# Driver.net
KiCad netlist of a schematic drawn in EAGLE
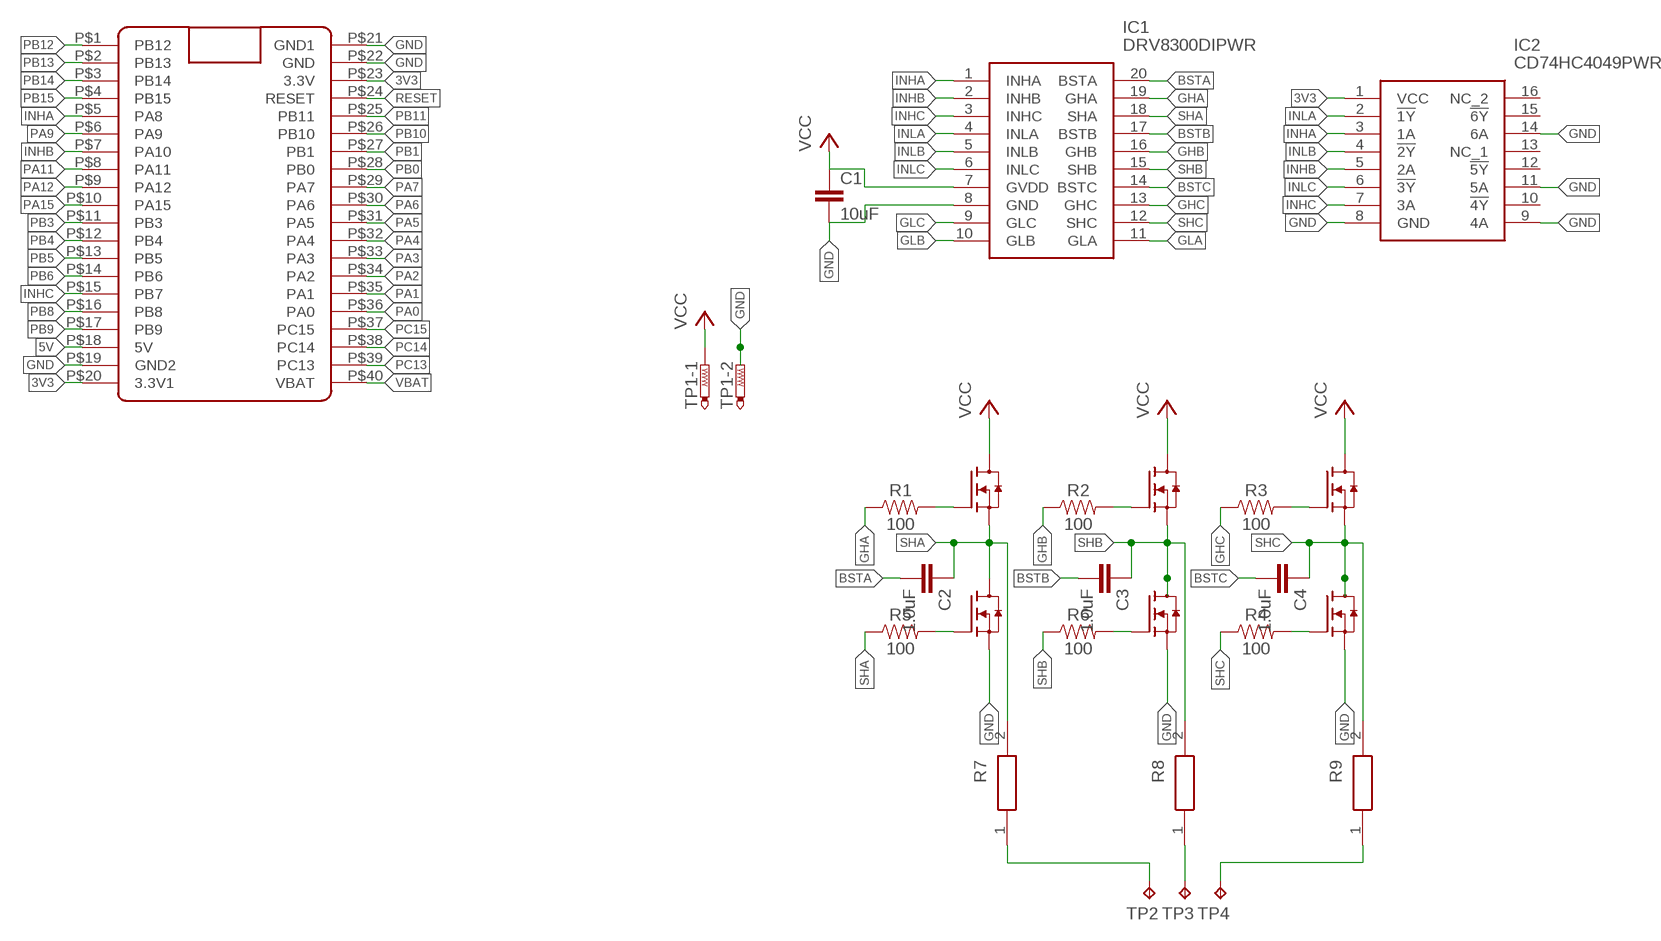
[diagram p0: schematic, sheet 1]

(export (version "E")
  (design (tool "Eeschema 10.0.6"))
  (components
    (comp (ref "C1")
      (value "10uF")
      (footprint "eagle-import:0603")
      (libsource (lib "eagle-import") (part "10UF-0603-6.3V-20%"))
    )
    (comp (ref "C2")
      (value "1.0uF")
      (footprint "eagle-import:0603")
      (libsource (lib "eagle-import") (part "1.0UF-0603-16V-10%"))
    )
    (comp (ref "C3")
      (value "1.0uF")
      (footprint "eagle-import:0603")
      (libsource (lib "eagle-import") (part "1.0UF-0603-16V-10%"))
    )
    (comp (ref "C4")
      (value "1.0uF")
      (footprint "eagle-import:0603")
      (libsource (lib "eagle-import") (part "1.0UF-0603-16V-10%"))
    )
    (comp (ref "IC1")
      (value "DRV8300DIPWR")
      (footprint "eagle-import:SOP65P640X120-20N")
      (fields (field (name "MOUSER_PART_NUMBER") "595-DRV8300DIPWR"))
      (libsource (lib "eagle-import") (part "DRV8300DIPWR"))
    )
    (comp (ref "IC2")
      (value "CD74HC4049PWR")
      (footprint "eagle-import:SOP65P640X120-16N")
      (fields (field (name "MOUSER_PART_NUMBER") "595-CD74HC4049PWR"))
      (libsource (lib "eagle-import") (part "CD74HC4049PWR"))
    )
    (comp (ref "R1")
      (value "100")
      (footprint "eagle-import:0603")
      (libsource (lib "eagle-import") (part "100OHM-0603-1/10W-1%"))
    )
    (comp (ref "R2")
      (value "100")
      (footprint "eagle-import:0603")
      (libsource (lib "eagle-import") (part "100OHM-0603-1/10W-1%"))
    )
    (comp (ref "R3")
      (value "100")
      (footprint "eagle-import:0603")
      (libsource (lib "eagle-import") (part "100OHM-0603-1/10W-1%"))
    )
    (comp (ref "R4")
      (value "100")
      (footprint "eagle-import:0603")
      (libsource (lib "eagle-import") (part "100OHM-0603-1/10W-1%"))
    )
    (comp (ref "R5")
      (value "100")
      (footprint "eagle-import:0603")
      (libsource (lib "eagle-import") (part "100OHM-0603-1/10W-1%"))
    )
    (comp (ref "R6")
      (value "100")
      (footprint "eagle-import:0603")
      (libsource (lib "eagle-import") (part "100OHM-0603-1/10W-1%"))
    )
    (comp (ref "R7")
      (value "CR2512-FX-51R1ELF")
      (footprint "eagle-import:RESC6331X75N")
      (fields (field (name "MOUSER_PART_NUMBER") "652-CR2512FX51R1ELF"))
      (libsource (lib "eagle-import") (part "CR2512-FX-51R1ELF"))
    )
    (comp (ref "R8")
      (value "CR2512-FX-51R1ELF")
      (footprint "eagle-import:RESC6331X75N")
      (fields (field (name "MOUSER_PART_NUMBER") "652-CR2512FX51R1ELF"))
      (libsource (lib "eagle-import") (part "CR2512-FX-51R1ELF"))
    )
    (comp (ref "R9")
      (value "CR2512-FX-51R1ELF")
      (footprint "eagle-import:RESC6331X75N")
      (fields (field (name "MOUSER_PART_NUMBER") "652-CR2512FX51R1ELF"))
      (libsource (lib "eagle-import") (part "CR2512-FX-51R1ELF"))
    )
    (comp (ref "TP1")
      (value "PTR2")
      (footprint "eagle-import:P2-38-17")
      (libsource (lib "eagle-import") (part "PTR2"))
    )
    (comp (ref "TP2")
      (value "TPTP20SQ")
      (footprint "eagle-import:TP20SQ")
      (libsource (lib "eagle-import") (part "TPTP20SQ"))
    )
    (comp (ref "TP3")
      (value "TPTP20SQ")
      (footprint "eagle-import:TP20SQ")
      (libsource (lib "eagle-import") (part "TPTP20SQ"))
    )
    (comp (ref "TP4")
      (value "TPTP20SQ")
      (footprint "eagle-import:TP20SQ")
      (libsource (lib "eagle-import") (part "TPTP20SQ"))
    )
    (comp (ref "U$1")
      (value "BLUE_PILL")
      (footprint "eagle-import:BLUE_PILL")
      (libsource (lib "eagle-import") (part "BLUE_PILL"))
    )
    (comp (ref "U$2")
      (value "IRLR7843")
      (footprint "eagle-import:TO252")
      (libsource (lib "eagle-import") (part "IRLR7843"))
    )
    (comp (ref "U$3")
      (value "IRLR7843")
      (footprint "eagle-import:TO252")
      (libsource (lib "eagle-import") (part "IRLR7843"))
    )
    (comp (ref "U$4")
      (value "IRLR7843")
      (footprint "eagle-import:TO252")
      (libsource (lib "eagle-import") (part "IRLR7843"))
    )
    (comp (ref "U$5")
      (value "IRLR7843")
      (footprint "eagle-import:TO252")
      (libsource (lib "eagle-import") (part "IRLR7843"))
    )
    (comp (ref "U$6")
      (value "IRLR7843")
      (footprint "eagle-import:TO252")
      (libsource (lib "eagle-import") (part "IRLR7843"))
    )
    (comp (ref "U$7")
      (value "IRLR7843")
      (footprint "eagle-import:TO252")
      (libsource (lib "eagle-import") (part "IRLR7843"))
    )
  )
  (nets
    (net (code "1") (name "3V3") (class "Default")
      (node (ref "IC2") (pin "1") (pinfunction "VCC_1") (pintype "bidirectional"))
      (node (ref "U$1") (pin "P$20") (pinfunction "3.3V1_P$20") (pintype "bidirectional"))
      (node (ref "U$1") (pin "P$23") (pinfunction "3.3V_P$23") (pintype "bidirectional"))
    )
    (net (code "2") (name "5V") (class "Default")
      (node (ref "U$1") (pin "P$18") (pinfunction "5V_P$18") (pintype "bidirectional"))
    )
    (net (code "3") (name "BSTA") (class "Default")
      (node (ref "C2") (pin "2") (pinfunction "2_2") (pintype "passive"))
      (node (ref "IC1") (pin "20") (pinfunction "BSTA_20") (pintype "bidirectional"))
    )
    (net (code "4") (name "BSTB") (class "Default")
      (node (ref "C3") (pin "2") (pinfunction "2_2") (pintype "passive"))
      (node (ref "IC1") (pin "17") (pinfunction "BSTB_17") (pintype "bidirectional"))
    )
    (net (code "5") (name "BSTC") (class "Default")
      (node (ref "C4") (pin "2") (pinfunction "2_2") (pintype "passive"))
      (node (ref "IC1") (pin "14") (pinfunction "BSTC_14") (pintype "bidirectional"))
    )
    (net (code "6") (name "GHA") (class "Default")
      (node (ref "IC1") (pin "19") (pinfunction "GHA_19") (pintype "bidirectional"))
      (node (ref "R1") (pin "1") (pinfunction "1_1") (pintype "passive"))
    )
    (net (code "7") (name "GHB") (class "Default")
      (node (ref "IC1") (pin "16") (pinfunction "GHB_16") (pintype "bidirectional"))
      (node (ref "R2") (pin "1") (pinfunction "1_1") (pintype "passive"))
    )
    (net (code "8") (name "GHC") (class "Default")
      (node (ref "IC1") (pin "13") (pinfunction "GHC_13") (pintype "bidirectional"))
      (node (ref "R3") (pin "1") (pinfunction "1_1") (pintype "passive"))
    )
    (net (code "9") (name "GLA") (class "Default")
      (node (ref "IC1") (pin "11") (pinfunction "GLA_11") (pintype "bidirectional"))
    )
    (net (code "10") (name "GLB") (class "Default")
      (node (ref "IC1") (pin "10") (pinfunction "GLB_10") (pintype "bidirectional"))
    )
    (net (code "11") (name "GLC") (class "Default")
      (node (ref "IC1") (pin "9") (pinfunction "GLC_9") (pintype "bidirectional"))
    )
    (net (code "12") (name "GND") (class "Default")
      (node (ref "C1") (pin "2") (pinfunction "2_2") (pintype "passive"))
      (node (ref "IC1") (pin "8") (pinfunction "GND_8") (pintype "bidirectional"))
      (node (ref "IC2") (pin "11") (pinfunction "5A_11") (pintype "bidirectional"))
      (node (ref "IC2") (pin "14") (pinfunction "6A_14") (pintype "bidirectional"))
      (node (ref "IC2") (pin "8") (pinfunction "GND_8") (pintype "bidirectional"))
      (node (ref "IC2") (pin "9") (pinfunction "4A_9") (pintype "bidirectional"))
      (node (ref "TP1") (pin "TP-2") (pinfunction "TP_TP-2") (pintype "input"))
      (node (ref "U$1") (pin "P$19") (pinfunction "GND2_P$19") (pintype "bidirectional"))
      (node (ref "U$1") (pin "P$21") (pinfunction "GND1_P$21") (pintype "power_in"))
      (node (ref "U$1") (pin "P$22") (pinfunction "GND_P$22") (pintype "bidirectional"))
      (node (ref "U$3") (pin "2") (pinfunction "S_2") (pintype "passive"))
      (node (ref "U$5") (pin "2") (pinfunction "S_2") (pintype "passive"))
      (node (ref "U$7") (pin "2") (pinfunction "S_2") (pintype "passive"))
    )
    (net (code "13") (name "INHA") (class "Default")
      (node (ref "IC1") (pin "1") (pinfunction "INHA_1") (pintype "bidirectional"))
      (node (ref "IC2") (pin "3") (pinfunction "1A_3") (pintype "bidirectional"))
      (node (ref "U$1") (pin "P$5") (pinfunction "PA8_P$5") (pintype "bidirectional"))
    )
    (net (code "14") (name "INHB") (class "Default")
      (node (ref "IC1") (pin "2") (pinfunction "INHB_2") (pintype "bidirectional"))
      (node (ref "IC2") (pin "5") (pinfunction "2A_5") (pintype "bidirectional"))
      (node (ref "U$1") (pin "P$7") (pinfunction "PA10_P$7") (pintype "bidirectional"))
    )
    (net (code "15") (name "INHC") (class "Default")
      (node (ref "IC1") (pin "3") (pinfunction "INHC_3") (pintype "bidirectional"))
      (node (ref "IC2") (pin "7") (pinfunction "3A_7") (pintype "bidirectional"))
      (node (ref "U$1") (pin "P$15") (pinfunction "PB7_P$15") (pintype "bidirectional"))
    )
    (net (code "16") (name "INLA") (class "Default")
      (node (ref "IC1") (pin "4") (pinfunction "INLA_4") (pintype "bidirectional"))
      (node (ref "IC2") (pin "2") (pinfunction "~{1Y}_2") (pintype "bidirectional"))
    )
    (net (code "17") (name "INLB") (class "Default")
      (node (ref "IC1") (pin "5") (pinfunction "INLB_5") (pintype "bidirectional"))
      (node (ref "IC2") (pin "4") (pinfunction "~{2Y}_4") (pintype "bidirectional"))
    )
    (net (code "18") (name "INLC") (class "Default")
      (node (ref "IC1") (pin "6") (pinfunction "INLC_6") (pintype "bidirectional"))
      (node (ref "IC2") (pin "6") (pinfunction "~{3Y}_6") (pintype "bidirectional"))
    )
    (net (code "19") (name "Net-(R7-Pad1)") (class "Default")
      (node (ref "R7") (pin "1") (pinfunction "1_1") (pintype "bidirectional"))
      (node (ref "TP2") (pin "TP") (pinfunction "TP_TP") (pintype "input"))
    )
    (net (code "20") (name "Net-(R8-Pad1)") (class "Default")
      (node (ref "R8") (pin "1") (pinfunction "1_1") (pintype "bidirectional"))
      (node (ref "TP3") (pin "TP") (pinfunction "TP_TP") (pintype "input"))
    )
    (net (code "21") (name "Net-(R9-Pad1)") (class "Default")
      (node (ref "R9") (pin "1") (pinfunction "1_1") (pintype "bidirectional"))
      (node (ref "TP4") (pin "TP") (pinfunction "TP_TP") (pintype "input"))
    )
    (net (code "22") (name "Net-(U$2-G)") (class "Default")
      (node (ref "R1") (pin "2") (pinfunction "2_2") (pintype "passive"))
      (node (ref "U$2") (pin "1") (pinfunction "G_1") (pintype "passive"))
    )
    (net (code "23") (name "Net-(U$3-G)") (class "Default")
      (node (ref "R5") (pin "2") (pinfunction "2_2") (pintype "passive"))
      (node (ref "U$3") (pin "1") (pinfunction "G_1") (pintype "passive"))
    )
    (net (code "24") (name "Net-(U$4-G)") (class "Default")
      (node (ref "R2") (pin "2") (pinfunction "2_2") (pintype "passive"))
      (node (ref "U$4") (pin "1") (pinfunction "G_1") (pintype "passive"))
    )
    (net (code "25") (name "Net-(U$5-G)") (class "Default")
      (node (ref "R6") (pin "2") (pinfunction "2_2") (pintype "passive"))
      (node (ref "U$5") (pin "1") (pinfunction "G_1") (pintype "passive"))
    )
    (net (code "26") (name "Net-(U$6-G)") (class "Default")
      (node (ref "R3") (pin "2") (pinfunction "2_2") (pintype "passive"))
      (node (ref "U$6") (pin "1") (pinfunction "G_1") (pintype "passive"))
    )
    (net (code "27") (name "Net-(U$7-G)") (class "Default")
      (node (ref "R4") (pin "2") (pinfunction "2_2") (pintype "passive"))
      (node (ref "U$7") (pin "1") (pinfunction "G_1") (pintype "passive"))
    )
    (net (code "28") (name "PA0") (class "Default")
      (node (ref "U$1") (pin "P$36") (pinfunction "PA0_P$36") (pintype "bidirectional"))
    )
    (net (code "29") (name "PA1") (class "Default")
      (node (ref "U$1") (pin "P$35") (pinfunction "PA1_P$35") (pintype "bidirectional"))
    )
    (net (code "30") (name "PA2") (class "Default")
      (node (ref "U$1") (pin "P$34") (pinfunction "PA2_P$34") (pintype "bidirectional"))
    )
    (net (code "31") (name "PA3") (class "Default")
      (node (ref "U$1") (pin "P$33") (pinfunction "PA3_P$33") (pintype "bidirectional"))
    )
    (net (code "32") (name "PA4") (class "Default")
      (node (ref "U$1") (pin "P$32") (pinfunction "PA4_P$32") (pintype "bidirectional"))
    )
    (net (code "33") (name "PA5") (class "Default")
      (node (ref "U$1") (pin "P$31") (pinfunction "PA5_P$31") (pintype "bidirectional"))
    )
    (net (code "34") (name "PA6") (class "Default")
      (node (ref "U$1") (pin "P$30") (pinfunction "PA6_P$30") (pintype "bidirectional"))
    )
    (net (code "35") (name "PA7") (class "Default")
      (node (ref "U$1") (pin "P$29") (pinfunction "PA7_P$29") (pintype "bidirectional"))
    )
    (net (code "36") (name "PA9") (class "Default")
      (node (ref "U$1") (pin "P$6") (pinfunction "PA9_P$6") (pintype "bidirectional"))
    )
    (net (code "37") (name "PA11") (class "Default")
      (node (ref "U$1") (pin "P$8") (pinfunction "PA11_P$8") (pintype "bidirectional"))
    )
    (net (code "38") (name "PA12") (class "Default")
      (node (ref "U$1") (pin "P$9") (pinfunction "PA12_P$9") (pintype "bidirectional"))
    )
    (net (code "39") (name "PA15") (class "Default")
      (node (ref "U$1") (pin "P$10") (pinfunction "PA15_P$10") (pintype "bidirectional"))
    )
    (net (code "40") (name "PB0") (class "Default")
      (node (ref "U$1") (pin "P$28") (pinfunction "PB0_P$28") (pintype "bidirectional"))
    )
    (net (code "41") (name "PB1") (class "Default")
      (node (ref "U$1") (pin "P$27") (pinfunction "PB1_P$27") (pintype "bidirectional"))
    )
    (net (code "42") (name "PB3") (class "Default")
      (node (ref "U$1") (pin "P$11") (pinfunction "PB3_P$11") (pintype "bidirectional"))
    )
    (net (code "43") (name "PB4") (class "Default")
      (node (ref "U$1") (pin "P$12") (pinfunction "PB4_P$12") (pintype "bidirectional"))
    )
    (net (code "44") (name "PB5") (class "Default")
      (node (ref "U$1") (pin "P$13") (pinfunction "PB5_P$13") (pintype "bidirectional"))
    )
    (net (code "45") (name "PB6") (class "Default")
      (node (ref "U$1") (pin "P$14") (pinfunction "PB6_P$14") (pintype "bidirectional"))
    )
    (net (code "46") (name "PB8") (class "Default")
      (node (ref "U$1") (pin "P$16") (pinfunction "PB8_P$16") (pintype "bidirectional"))
    )
    (net (code "47") (name "PB9") (class "Default")
      (node (ref "U$1") (pin "P$17") (pinfunction "PB9_P$17") (pintype "bidirectional"))
    )
    (net (code "48") (name "PB10") (class "Default")
      (node (ref "U$1") (pin "P$26") (pinfunction "PB10_P$26") (pintype "bidirectional"))
    )
    (net (code "49") (name "PB11") (class "Default")
      (node (ref "U$1") (pin "P$25") (pinfunction "PB11_P$25") (pintype "bidirectional"))
    )
    (net (code "50") (name "PB12") (class "Default")
      (node (ref "U$1") (pin "P$1") (pinfunction "PB12_P$1") (pintype "bidirectional"))
    )
    (net (code "51") (name "PB13") (class "Default")
      (node (ref "U$1") (pin "P$2") (pinfunction "PB13_P$2") (pintype "bidirectional"))
    )
    (net (code "52") (name "PB14") (class "Default")
      (node (ref "U$1") (pin "P$3") (pinfunction "PB14_P$3") (pintype "bidirectional"))
    )
    (net (code "53") (name "PB15") (class "Default")
      (node (ref "U$1") (pin "P$4") (pinfunction "PB15_P$4") (pintype "bidirectional"))
    )
    (net (code "54") (name "PC13") (class "Default")
      (node (ref "U$1") (pin "P$39") (pinfunction "PC13_P$39") (pintype "bidirectional"))
    )
    (net (code "55") (name "PC14") (class "Default")
      (node (ref "U$1") (pin "P$38") (pinfunction "PC14_P$38") (pintype "bidirectional"))
    )
    (net (code "56") (name "PC15") (class "Default")
      (node (ref "U$1") (pin "P$37") (pinfunction "PC15_P$37") (pintype "bidirectional"))
    )
    (net (code "57") (name "RESET") (class "Default")
      (node (ref "U$1") (pin "P$24") (pinfunction "RESET_P$24") (pintype "bidirectional"))
    )
    (net (code "58") (name "SHA") (class "Default")
      (node (ref "C2") (pin "1") (pinfunction "1_1") (pintype "passive"))
      (node (ref "IC1") (pin "18") (pinfunction "SHA_18") (pintype "bidirectional"))
      (node (ref "R5") (pin "1") (pinfunction "1_1") (pintype "passive"))
      (node (ref "R7") (pin "2") (pinfunction "2_2") (pintype "bidirectional"))
      (node (ref "U$2") (pin "2") (pinfunction "S_2") (pintype "passive"))
      (node (ref "U$3") (pin "3") (pinfunction "D_3") (pintype "passive"))
    )
    (net (code "59") (name "SHB") (class "Default")
      (node (ref "C3") (pin "1") (pinfunction "1_1") (pintype "passive"))
      (node (ref "IC1") (pin "15") (pinfunction "SHB_15") (pintype "bidirectional"))
      (node (ref "R6") (pin "1") (pinfunction "1_1") (pintype "passive"))
      (node (ref "R8") (pin "2") (pinfunction "2_2") (pintype "bidirectional"))
      (node (ref "U$4") (pin "2") (pinfunction "S_2") (pintype "passive"))
      (node (ref "U$5") (pin "3") (pinfunction "D_3") (pintype "passive"))
    )
    (net (code "60") (name "SHC") (class "Default")
      (node (ref "C4") (pin "1") (pinfunction "1_1") (pintype "passive"))
      (node (ref "IC1") (pin "12") (pinfunction "SHC_12") (pintype "bidirectional"))
      (node (ref "R4") (pin "1") (pinfunction "1_1") (pintype "passive"))
      (node (ref "R9") (pin "2") (pinfunction "2_2") (pintype "bidirectional"))
      (node (ref "U$6") (pin "2") (pinfunction "S_2") (pintype "passive"))
      (node (ref "U$7") (pin "3") (pinfunction "D_3") (pintype "passive"))
    )
    (net (code "61") (name "VBAT") (class "Default")
      (node (ref "U$1") (pin "P$40") (pinfunction "VBAT_P$40") (pintype "bidirectional"))
    )
    (net (code "62") (name "VCC") (class "Default")
      (node (ref "C1") (pin "1") (pinfunction "1_1") (pintype "passive"))
      (node (ref "IC1") (pin "7") (pinfunction "GVDD_7") (pintype "bidirectional"))
      (node (ref "TP1") (pin "TP-1") (pinfunction "TP_TP-1") (pintype "input"))
      (node (ref "U$2") (pin "3") (pinfunction "D_3") (pintype "passive"))
      (node (ref "U$4") (pin "3") (pinfunction "D_3") (pintype "passive"))
      (node (ref "U$6") (pin "3") (pinfunction "D_3") (pintype "passive"))
    )
    (net (code "63") (name "unconnected-(IC2-NC_1-Pad13)") (class "Default")
      (node (ref "IC2") (pin "13") (pinfunction "NC_1_13") (pintype "bidirectional"))
    )
    (net (code "64") (name "unconnected-(IC2-NC_2-Pad16)") (class "Default")
      (node (ref "IC2") (pin "16") (pinfunction "NC_2_16") (pintype "bidirectional"))
    )
    (net (code "65") (name "unconnected-(IC2-~{4Y}-Pad10)") (class "Default")
      (node (ref "IC2") (pin "10") (pinfunction "~{4Y}_10") (pintype "bidirectional"))
    )
    (net (code "66") (name "unconnected-(IC2-~{5Y}-Pad12)") (class "Default")
      (node (ref "IC2") (pin "12") (pinfunction "~{5Y}_12") (pintype "bidirectional"))
    )
    (net (code "67") (name "unconnected-(IC2-~{6Y}-Pad15)") (class "Default")
      (node (ref "IC2") (pin "15") (pinfunction "~{6Y}_15") (pintype "bidirectional"))
    )
  )
)
